# briefkasten.net
KiCad netlist of a schematic drawn in EAGLE
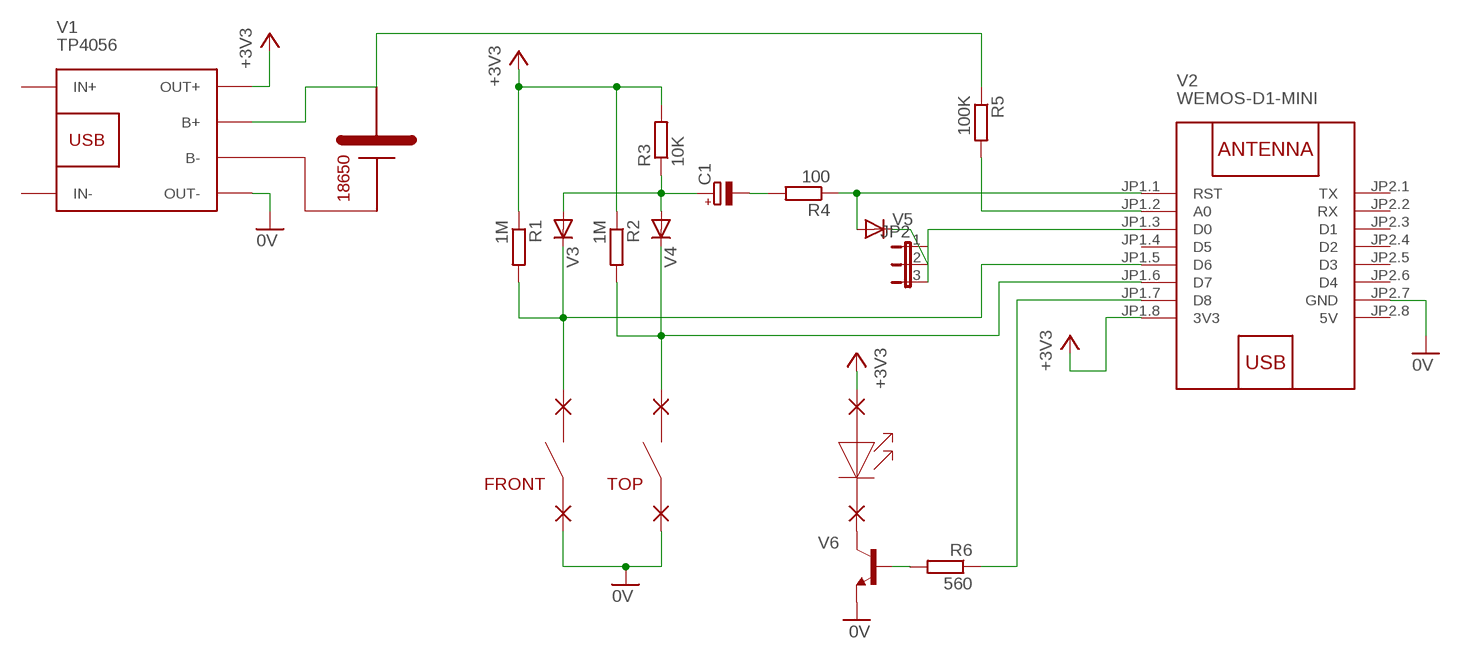
[diagram p0: schematic, sheet 1]

(export (version "E")
  (design (tool "Eeschema 10.0.6"))
  (components
    (comp (ref "C1")
      (value "CPOL-EUE2.5-5")
      (footprint "eagle-import:E2,5-5")
      (libsource (lib "eagle-import") (part "CPOL-EUE2.5-5"))
    )
    (comp (ref "JP2")
      (value "JP2E")
      (footprint "eagle-import:JP2")
      (libsource (lib "eagle-import") (part "JP2E"))
    )
    (comp (ref "PAD7")
      (value "1,6/0,9")
      (footprint "eagle-import:1,6_0,9")
      (libsource (lib "eagle-import") (part "1,6/0,9"))
    )
    (comp (ref "PAD8")
      (value "1,6/0,9")
      (footprint "eagle-import:1,6_0,9")
      (libsource (lib "eagle-import") (part "1,6/0,9"))
    )
    (comp (ref "PAD9")
      (value "1,6/0,9")
      (footprint "eagle-import:1,6_0,9")
      (libsource (lib "eagle-import") (part "1,6/0,9"))
    )
    (comp (ref "PAD10")
      (value "1,6/0,9")
      (footprint "eagle-import:1,6_0,9")
      (libsource (lib "eagle-import") (part "1,6/0,9"))
    )
    (comp (ref "PAD11")
      (value "1,6/0,9")
      (footprint "eagle-import:1,6_0,9")
      (libsource (lib "eagle-import") (part "1,6/0,9"))
    )
    (comp (ref "PAD12")
      (value "1,6/0,9")
      (footprint "eagle-import:1,6_0,9")
      (libsource (lib "eagle-import") (part "1,6/0,9"))
    )
    (comp (ref "R1")
      (value "1M")
      (footprint "eagle-import:0207_7")
      (libsource (lib "eagle-import") (part "R-EU_0207/7"))
    )
    (comp (ref "R2")
      (value "1M")
      (footprint "eagle-import:0207_7")
      (libsource (lib "eagle-import") (part "R-EU_0207/7"))
    )
    (comp (ref "R3")
      (value "10K")
      (footprint "eagle-import:0207_7")
      (libsource (lib "eagle-import") (part "R-EU_0207/7"))
    )
    (comp (ref "R4")
      (value "100")
      (footprint "eagle-import:0309V")
      (libsource (lib "eagle-import") (part "R-EU_0309/V"))
    )
    (comp (ref "R5")
      (value "100K")
      (footprint "eagle-import:0207_7")
      (libsource (lib "eagle-import") (part "R-EU_0207/7"))
    )
    (comp (ref "R6")
      (value "560")
      (footprint "eagle-import:0207_7")
      (libsource (lib "eagle-import") (part "R-EU_0207/7"))
    )
    (comp (ref "V1")
      (value "TP4056")
      (footprint "eagle-import:BATTERY-CHARGER-LI-PROT")
      (libsource (lib "eagle-import") (part "BATTERY-CHARGER-LI-PROT"))
    )
    (comp (ref "V2")
      (value "WEMOS-D1-MINI")
      (footprint "eagle-import:WEMOS-D1-MINI")
      (libsource (lib "eagle-import") (part "WEMOS-D1-MINI"))
    )
    (comp (ref "V3")
      (value "1N4148DO35-7")
      (footprint "eagle-import:DO35-7")
      (libsource (lib "eagle-import") (part "1N4148DO35-7"))
    )
    (comp (ref "V4")
      (value "1N4148DO35-7")
      (footprint "eagle-import:DO35-7")
      (libsource (lib "eagle-import") (part "1N4148DO35-7"))
    )
    (comp (ref "V5")
      (value "DIODE-D-2.5")
      (footprint "eagle-import:D-2.5")
      (libsource (lib "eagle-import") (part "DIODE-D-2.5"))
    )
    (comp (ref "V6")
      (value "-NPN-TO92-EBC")
      (footprint "eagle-import:TO92-EBC")
      (libsource (lib "eagle-import") (part "-NPN-TO92-EBC"))
    )
  )
  (nets
    (net (code "1") (name "+3V3") (class "Default")
      (node (ref "PAD8") (pin "1") (pinfunction "P_1") (pintype "passive"))
      (node (ref "R1") (pin "1") (pinfunction "1_1") (pintype "passive"))
      (node (ref "R2") (pin "1") (pinfunction "1_1") (pintype "passive"))
      (node (ref "R3") (pin "2") (pinfunction "2_2") (pintype "passive"))
      (node (ref "V1") (pin "OUT+") (pinfunction "OUT+_OUT+") (pintype "bidirectional"))
      (node (ref "V2") (pin "JP1.8") (pinfunction "3V3_JP1.8") (pintype "power_in"))
    )
    (net (code "2") (name "/5V") (class "Default")
      (node (ref "V2") (pin "JP2.8") (pinfunction "5V_JP2.8") (pintype "power_in"))
    )
    (net (code "3") (name "0V") (class "Default")
      (node (ref "PAD10") (pin "1") (pinfunction "P_1") (pintype "passive"))
      (node (ref "PAD12") (pin "1") (pinfunction "P_1") (pintype "passive"))
      (node (ref "V1") (pin "OUT-") (pinfunction "OUT-_OUT-") (pintype "bidirectional"))
      (node (ref "V2") (pin "JP2.7") (pinfunction "GND_JP2.7") (pintype "power_in"))
      (node (ref "V6") (pin "E") (pinfunction "E_E") (pintype "passive"))
    )
    (net (code "4") (name "Net-(C1-Pad+)") (class "Default")
      (node (ref "C1") (pin "+") (pinfunction "+_+") (pintype "passive"))
      (node (ref "R3") (pin "1") (pinfunction "1_1") (pintype "passive"))
      (node (ref "V3") (pin "A") (pinfunction "A_A") (pintype "passive"))
      (node (ref "V4") (pin "A") (pinfunction "A_A") (pintype "passive"))
    )
    (net (code "5") (name "Net-(C1-Pad-)") (class "Default")
      (node (ref "C1") (pin "-") (pinfunction "-_-") (pintype "passive"))
      (node (ref "R4") (pin "2") (pinfunction "2_2") (pintype "passive"))
    )
    (net (code "6") (name "Net-(JP2-Pad2)") (class "Default")
      (node (ref "JP2") (pin "2") (pinfunction "2_2") (pintype "passive"))
      (node (ref "V5") (pin "C") (pinfunction "C_C") (pintype "passive"))
    )
    (net (code "7") (name "Net-(PAD7-P)") (class "Default")
      (node (ref "PAD7") (pin "1") (pinfunction "P_1") (pintype "passive"))
      (node (ref "V6") (pin "C") (pinfunction "C_C") (pintype "passive"))
    )
    (net (code "8") (name "Net-(PAD9-P)") (class "Default")
      (node (ref "PAD9") (pin "1") (pinfunction "P_1") (pintype "passive"))
      (node (ref "R1") (pin "2") (pinfunction "2_2") (pintype "passive"))
      (node (ref "V2") (pin "JP1.5") (pinfunction "D6_JP1.5") (pintype "bidirectional"))
      (node (ref "V3") (pin "C") (pinfunction "C_C") (pintype "passive"))
    )
    (net (code "9") (name "Net-(PAD11-P)") (class "Default")
      (node (ref "PAD11") (pin "1") (pinfunction "P_1") (pintype "passive"))
      (node (ref "R2") (pin "2") (pinfunction "2_2") (pintype "passive"))
      (node (ref "V2") (pin "JP1.6") (pinfunction "D7_JP1.6") (pintype "bidirectional"))
      (node (ref "V4") (pin "C") (pinfunction "C_C") (pintype "passive"))
    )
    (net (code "10") (name "Net-(R5-Pad1)") (class "Default")
      (node (ref "R5") (pin "1") (pinfunction "1_1") (pintype "passive"))
      (node (ref "V1") (pin "B+") (pinfunction "B+_B+") (pintype "bidirectional"))
    )
    (net (code "11") (name "Net-(R6-Pad2)") (class "Default")
      (node (ref "R6") (pin "2") (pinfunction "2_2") (pintype "passive"))
      (node (ref "V6") (pin "B") (pinfunction "B_B") (pintype "passive"))
    )
    (net (code "12") (name "Net-(V2-A0)") (class "Default")
      (node (ref "R5") (pin "2") (pinfunction "2_2") (pintype "passive"))
      (node (ref "V2") (pin "JP1.2") (pinfunction "A0_JP1.2") (pintype "bidirectional"))
    )
    (net (code "13") (name "Net-(V2-D0)") (class "Default")
      (node (ref "JP2") (pin "3") (pinfunction "3_3") (pintype "passive"))
      (node (ref "V2") (pin "JP1.3") (pinfunction "D0_JP1.3") (pintype "bidirectional"))
    )
    (net (code "14") (name "Net-(V2-D8)") (class "Default")
      (node (ref "R6") (pin "1") (pinfunction "1_1") (pintype "passive"))
      (node (ref "V2") (pin "JP1.7") (pinfunction "D8_JP1.7") (pintype "bidirectional"))
    )
    (net (code "15") (name "Net-(V2-RST)") (class "Default")
      (node (ref "R4") (pin "1") (pinfunction "1_1") (pintype "passive"))
      (node (ref "V2") (pin "JP1.1") (pinfunction "RST_JP1.1") (pintype "bidirectional"))
      (node (ref "V5") (pin "A") (pinfunction "A_A") (pintype "passive"))
    )
    (net (code "16") (name "unconnected-(JP2-Pad1)") (class "Default")
      (node (ref "JP2") (pin "1") (pinfunction "1_1") (pintype "passive"))
    )
    (net (code "17") (name "unconnected-(V1-PadB-)") (class "Default")
      (node (ref "V1") (pin "B-") (pinfunction "B-_B-") (pintype "bidirectional"))
    )
    (net (code "18") (name "unconnected-(V1-PadIN+)") (class "Default")
      (node (ref "V1") (pin "IN+") (pinfunction "IN+_IN+") (pintype "bidirectional"))
    )
    (net (code "19") (name "unconnected-(V1-PadIN-)") (class "Default")
      (node (ref "V1") (pin "IN-") (pinfunction "IN-_IN-") (pintype "bidirectional"))
    )
    (net (code "20") (name "unconnected-(V2-D1-PadJP2.3)") (class "Default")
      (node (ref "V2") (pin "JP2.3") (pinfunction "D1_JP2.3") (pintype "bidirectional"))
    )
    (net (code "21") (name "unconnected-(V2-D2-PadJP2.4)") (class "Default")
      (node (ref "V2") (pin "JP2.4") (pinfunction "D2_JP2.4") (pintype "bidirectional"))
    )
    (net (code "22") (name "unconnected-(V2-D3-PadJP2.5)") (class "Default")
      (node (ref "V2") (pin "JP2.5") (pinfunction "D3_JP2.5") (pintype "bidirectional"))
    )
    (net (code "23") (name "unconnected-(V2-D4-PadJP2.6)") (class "Default")
      (node (ref "V2") (pin "JP2.6") (pinfunction "D4_JP2.6") (pintype "bidirectional"))
    )
    (net (code "24") (name "unconnected-(V2-D5-PadJP1.4)") (class "Default")
      (node (ref "V2") (pin "JP1.4") (pinfunction "D5_JP1.4") (pintype "bidirectional"))
    )
    (net (code "25") (name "unconnected-(V2-RX-PadJP2.2)") (class "Default")
      (node (ref "V2") (pin "JP2.2") (pinfunction "RX_JP2.2") (pintype "bidirectional"))
    )
    (net (code "26") (name "unconnected-(V2-TX-PadJP2.1)") (class "Default")
      (node (ref "V2") (pin "JP2.1") (pinfunction "TX_JP2.1") (pintype "bidirectional"))
    )
  )
)
